# FRA_Sensor_TGS2xxx.net
KiCad netlist of a schematic drawn in EAGLE
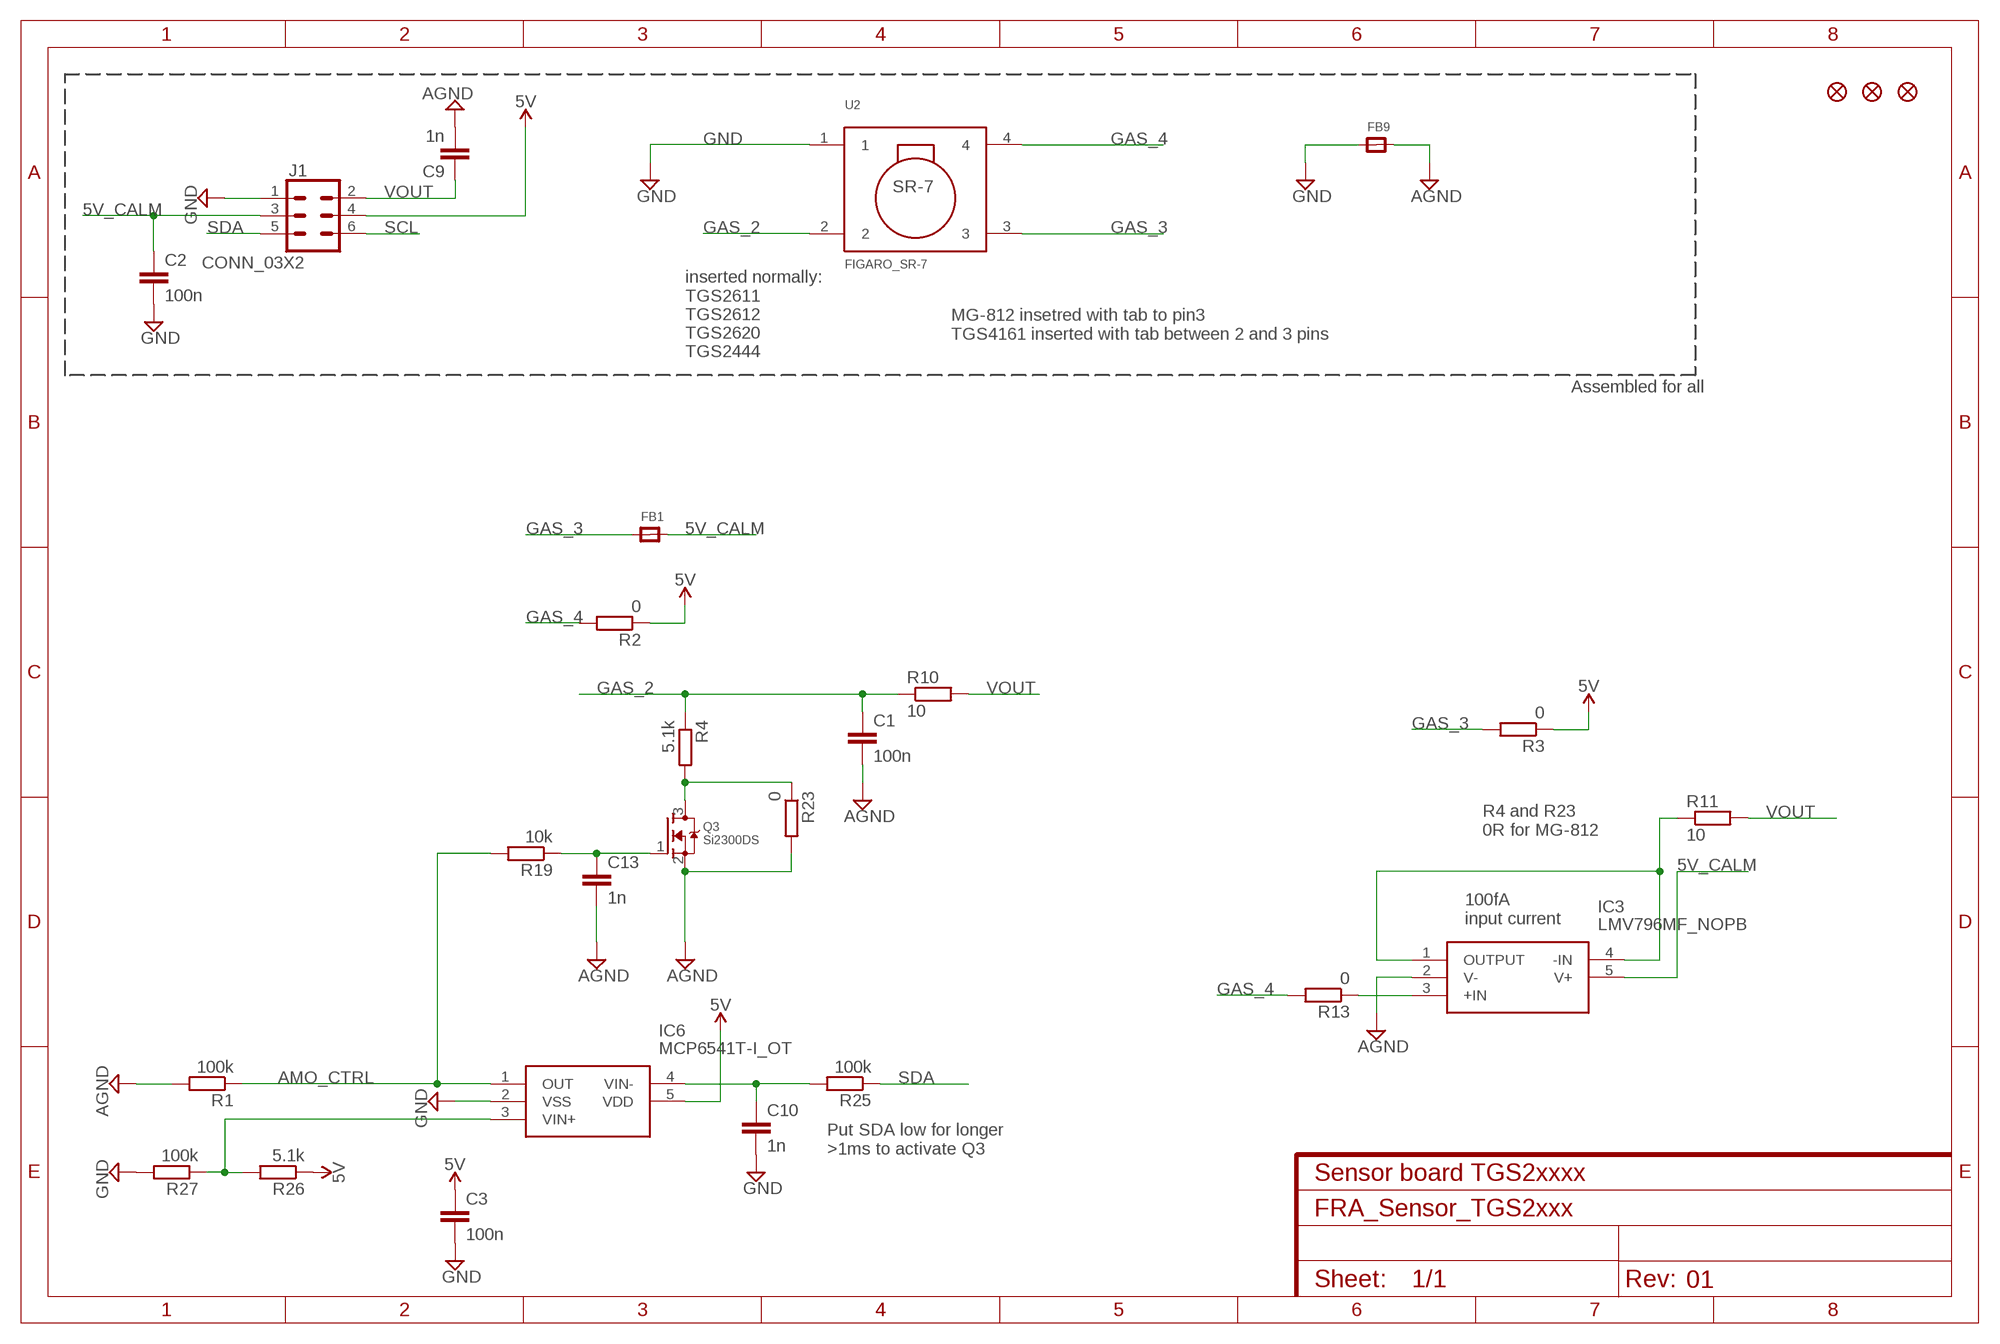
[diagram p0: schematic, sheet 1]

(export (version "E")
  (design (tool "Eeschema 10.0.6"))
  (components
    (comp (ref "C1")
      (value "100n")
      (footprint "eagle-import:C0603K")
      (fields (field (name "PARTNO") "GRM188R71C104KA01D"))
      (libsource (lib "eagle-import") (part "C-EUC0603K"))
    )
    (comp (ref "C2")
      (value "100n")
      (footprint "eagle-import:C0603K")
      (fields (field (name "PARTNO") "GRM188R71C104KA01D"))
      (libsource (lib "eagle-import") (part "C-EUC0603K"))
    )
    (comp (ref "C3")
      (value "100n")
      (footprint "eagle-import:C0603K")
      (fields (field (name "PARTNO") "GRM188R71C104KA01D"))
      (libsource (lib "eagle-import") (part "C-EUC0603K"))
    )
    (comp (ref "C9")
      (value "1n")
      (footprint "eagle-import:C0603K")
      (fields (field (name "PARTNO") "GRM188R71H102KA01D"))
      (libsource (lib "eagle-import") (part "C-EUC0603K"))
    )
    (comp (ref "C10")
      (value "1n")
      (footprint "eagle-import:C0603K")
      (fields (field (name "PARTNO") "GRM188R71H102KA01D"))
      (libsource (lib "eagle-import") (part "C-EUC0603K"))
    )
    (comp (ref "C13")
      (value "1n")
      (footprint "eagle-import:C0603K")
      (fields (field (name "PARTNO") "GRM188R71H102KA01D"))
      (libsource (lib "eagle-import") (part "C-EUC0603K"))
    )
    (comp (ref "FB1")
      (value "FERRITE")
      (footprint "eagle-import:0603")
      (fields (field (name "PARTNO") "BLM18PG121SN1D"))
      (libsource (lib "eagle-import") (part "FERRITE"))
    )
    (comp (ref "FB9")
      (value "FERRITE")
      (footprint "eagle-import:0603")
      (fields (field (name "PARTNO") "BLM18PG121SN1D"))
      (libsource (lib "eagle-import") (part "FERRITE"))
    )
    (comp (ref "FID1")
      (value "FIDUCIAL\"\"")
      (footprint "eagle-import:FIDUCIAL_1MM")
      (libsource (lib "eagle-import") (part "FIDUCIAL{dblquote}{dblquote}"))
    )
    (comp (ref "FID2")
      (value "FIDUCIAL\"\"")
      (footprint "eagle-import:FIDUCIAL_1MM")
      (libsource (lib "eagle-import") (part "FIDUCIAL{dblquote}{dblquote}"))
    )
    (comp (ref "FID4")
      (value "FIDUCIAL\"\"")
      (footprint "eagle-import:FIDUCIAL_1MM")
      (libsource (lib "eagle-import") (part "FIDUCIAL{dblquote}{dblquote}"))
    )
    (comp (ref "IC3")
      (value "LMV796MF_NOPB")
      (footprint "eagle-import:SOT95P280X145-5N")
      (fields
        (field (name "MANUFACTURER_PART_NUMBER") "LMV796MF/NOPB")
        (field (name "MOUSER_PART_NUMBER") "926-LMV796MF/NOPB")
        (field (name "PARTNO") "LMV796MF")
      )
      (libsource (lib "eagle-import") (part "LMV796MF_NOPB"))
    )
    (comp (ref "IC6")
      (value "MCP6541T-I_OT")
      (footprint "eagle-import:SOT95P270X145-5N")
      (fields
        (field (name "MANUFACTURER_PART_NUMBER") "MCP6541T-I/OT")
        (field (name "MOUSER_PART_NUMBER") "579-MCP6541T-I/OT")
      )
      (libsource (lib "eagle-import") (part "MCP6541T-I_OT"))
    )
    (comp (ref "J1")
      (value "CONN_03X2")
      (footprint "eagle-import:WE_61200621621")
      (fields (field (name "PARTNO") "30306-6002HB"))
      (libsource (lib "eagle-import") (part "CONN_03X2_WE_61200621621"))
    )
    (comp (ref "Q3")
      (value "Si2300DS")
      (footprint "eagle-import:SOT23")
      (fields (field (name "PARTNO") "SI2300DS-T1-GE3"))
      (libsource (lib "eagle-import") (part "MOSFET-NREFLOW"))
    )
    (comp (ref "R1")
      (value "100k")
      (footprint "eagle-import:R0603")
      (fields (field (name "PARTNO") "CRCW0603100KFKEA"))
      (libsource (lib "eagle-import") (part "R-EU_R0603"))
    )
    (comp (ref "R2")
      (value "0")
      (footprint "eagle-import:R0603")
      (fields (field (name "PARTNO") "CRCW06030000Z0EA"))
      (libsource (lib "eagle-import") (part "R-EU_R0603"))
    )
    (comp (ref "R3")
      (value "0")
      (footprint "eagle-import:R0603")
      (fields (field (name "PARTNO") "CRCW06030000Z0EA"))
      (libsource (lib "eagle-import") (part "R-EU_R0603"))
    )
    (comp (ref "R4")
      (value "5.1k")
      (footprint "eagle-import:R0603")
      (fields (field (name "PARTNO") "CRCW06035K10FKEA"))
      (libsource (lib "eagle-import") (part "R-EU_R0603"))
    )
    (comp (ref "R10")
      (value "10")
      (footprint "eagle-import:R0603")
      (fields (field (name "PARTNO") "CRCW060310R0FKEA"))
      (libsource (lib "eagle-import") (part "R-EU_R0603"))
    )
    (comp (ref "R11")
      (value "10")
      (footprint "eagle-import:R0603")
      (fields (field (name "PARTNO") "CRCW060310R0FKEA"))
      (libsource (lib "eagle-import") (part "R-EU_R0603"))
    )
    (comp (ref "R13")
      (value "0")
      (footprint "eagle-import:R0603")
      (fields (field (name "PARTNO") "CRCW06030000Z0EA"))
      (libsource (lib "eagle-import") (part "R-EU_R0603"))
    )
    (comp (ref "R19")
      (value "10k")
      (footprint "eagle-import:R0603")
      (fields (field (name "PARTNO") "CRCW060310K0FKEA"))
      (libsource (lib "eagle-import") (part "R-EU_R0603"))
    )
    (comp (ref "R23")
      (value "0")
      (footprint "eagle-import:R0603")
      (fields (field (name "PARTNO") "CRCW06030000Z0EA"))
      (libsource (lib "eagle-import") (part "R-EU_R0603"))
    )
    (comp (ref "R25")
      (value "100k")
      (footprint "eagle-import:R0603")
      (fields (field (name "PARTNO") "CRCW0603100KFKEA"))
      (libsource (lib "eagle-import") (part "R-EU_R0603"))
    )
    (comp (ref "R26")
      (value "5.1k")
      (footprint "eagle-import:R0603")
      (fields (field (name "PARTNO") "CRCW06035K10FKEA"))
      (libsource (lib "eagle-import") (part "R-EU_R0603"))
    )
    (comp (ref "R27")
      (value "100k")
      (footprint "eagle-import:R0603")
      (fields (field (name "PARTNO") "CRCW0603100KFKEA"))
      (libsource (lib "eagle-import") (part "R-EU_R0603"))
    )
    (comp (ref "U2")
      (value "FIGARO_SR-7")
      (footprint "eagle-import:FIGARO-SR7")
      (fields (field (name "PARTNO") "installed_by_customer"))
      (libsource (lib "eagle-import") (part "FIGARO_SR-7"))
    )
  )
  (nets
    (net (code "1") (name "/5V_CALM") (class "Default")
      (node (ref "C2") (pin "1") (pinfunction "1_1") (pintype "passive"))
      (node (ref "FB1") (pin "2") (pinfunction "P$2_2") (pintype "passive"))
      (node (ref "IC3") (pin "5") (pinfunction "V+_5") (pintype "bidirectional"))
      (node (ref "J1") (pin "3") (pinfunction "3_3") (pintype "bidirectional"))
    )
    (net (code "2") (name "/AMO_CTRL") (class "Default")
      (node (ref "IC6") (pin "1") (pinfunction "OUT_1") (pintype "output"))
      (node (ref "R1") (pin "1") (pinfunction "1_1") (pintype "passive"))
      (node (ref "R19") (pin "2") (pinfunction "2_2") (pintype "passive"))
    )
    (net (code "3") (name "/GAS_2") (class "Default")
      (node (ref "C1") (pin "1") (pinfunction "1_1") (pintype "passive"))
      (node (ref "R10") (pin "1") (pinfunction "1_1") (pintype "passive"))
      (node (ref "R4") (pin "1") (pinfunction "1_1") (pintype "passive"))
      (node (ref "U2") (pin "2") (pinfunction "2_2") (pintype "bidirectional"))
    )
    (net (code "4") (name "/GAS_3") (class "Default")
      (node (ref "FB1") (pin "1") (pinfunction "P$1_1") (pintype "passive"))
      (node (ref "R3") (pin "2") (pinfunction "2_2") (pintype "passive"))
      (node (ref "U2") (pin "3") (pinfunction "3_3") (pintype "bidirectional"))
    )
    (net (code "5") (name "/GAS_4") (class "Default")
      (node (ref "R13") (pin "2") (pinfunction "2_2") (pintype "passive"))
      (node (ref "R2") (pin "2") (pinfunction "2_2") (pintype "passive"))
      (node (ref "U2") (pin "4") (pinfunction "4_4") (pintype "bidirectional"))
    )
    (net (code "6") (name "/SCL") (class "Default")
      (node (ref "J1") (pin "6") (pinfunction "6_6") (pintype "bidirectional"))
    )
    (net (code "7") (name "/SDA") (class "Default")
      (node (ref "J1") (pin "5") (pinfunction "5_5") (pintype "bidirectional"))
      (node (ref "R25") (pin "1") (pinfunction "1_1") (pintype "passive"))
    )
    (net (code "8") (name "/VOUT") (class "Default")
      (node (ref "C9") (pin "1") (pinfunction "1_1") (pintype "passive"))
      (node (ref "J1") (pin "2") (pinfunction "2_2") (pintype "bidirectional"))
      (node (ref "R10") (pin "2") (pinfunction "2_2") (pintype "passive"))
      (node (ref "R11") (pin "2") (pinfunction "2_2") (pintype "passive"))
    )
    (net (code "9") (name "5V") (class "Default")
      (node (ref "C3") (pin "1") (pinfunction "1_1") (pintype "passive"))
      (node (ref "IC6") (pin "5") (pinfunction "VDD_5") (pintype "power_in"))
      (node (ref "J1") (pin "4") (pinfunction "4_4") (pintype "bidirectional"))
      (node (ref "R2") (pin "1") (pinfunction "1_1") (pintype "passive"))
      (node (ref "R26") (pin "1") (pinfunction "1_1") (pintype "passive"))
      (node (ref "R3") (pin "1") (pinfunction "1_1") (pintype "passive"))
    )
    (net (code "10") (name "AGND") (class "Default")
      (node (ref "C1") (pin "2") (pinfunction "2_2") (pintype "passive"))
      (node (ref "C13") (pin "2") (pinfunction "2_2") (pintype "passive"))
      (node (ref "C9") (pin "2") (pinfunction "2_2") (pintype "passive"))
      (node (ref "FB9") (pin "2") (pinfunction "P$2_2") (pintype "passive"))
      (node (ref "IC3") (pin "2") (pinfunction "V-_2") (pintype "bidirectional"))
      (node (ref "Q3") (pin "2") (pinfunction "S_2") (pintype "bidirectional"))
      (node (ref "R1") (pin "2") (pinfunction "2_2") (pintype "passive"))
      (node (ref "R23") (pin "2") (pinfunction "2_2") (pintype "passive"))
    )
    (net (code "11") (name "GND") (class "Default")
      (node (ref "C10") (pin "2") (pinfunction "2_2") (pintype "passive"))
      (node (ref "C2") (pin "2") (pinfunction "2_2") (pintype "passive"))
      (node (ref "C3") (pin "2") (pinfunction "2_2") (pintype "passive"))
      (node (ref "FB9") (pin "1") (pinfunction "P$1_1") (pintype "passive"))
      (node (ref "IC6") (pin "2") (pinfunction "VSS_2") (pintype "power_in"))
      (node (ref "J1") (pin "1") (pinfunction "1_1") (pintype "bidirectional"))
      (node (ref "R27") (pin "2") (pinfunction "2_2") (pintype "passive"))
      (node (ref "U2") (pin "1") (pinfunction "1_1") (pintype "bidirectional"))
    )
    (net (code "12") (name "Net-(IC3-+IN)") (class "Default")
      (node (ref "IC3") (pin "3") (pinfunction "+IN_3") (pintype "input"))
      (node (ref "R13") (pin "1") (pinfunction "1_1") (pintype "passive"))
    )
    (net (code "13") (name "Net-(IC3--IN)") (class "Default")
      (node (ref "IC3") (pin "1") (pinfunction "OUTPUT_1") (pintype "output"))
      (node (ref "IC3") (pin "4") (pinfunction "-IN_4") (pintype "input"))
      (node (ref "R11") (pin "1") (pinfunction "1_1") (pintype "passive"))
    )
    (net (code "14") (name "Net-(IC6-VIN+)") (class "Default")
      (node (ref "IC6") (pin "3") (pinfunction "VIN+_3") (pintype "input"))
      (node (ref "R26") (pin "2") (pinfunction "2_2") (pintype "passive"))
      (node (ref "R27") (pin "1") (pinfunction "1_1") (pintype "passive"))
    )
    (net (code "15") (name "Net-(IC6-VIN-)") (class "Default")
      (node (ref "C10") (pin "1") (pinfunction "1_1") (pintype "passive"))
      (node (ref "IC6") (pin "4") (pinfunction "VIN-_4") (pintype "input"))
      (node (ref "R25") (pin "2") (pinfunction "2_2") (pintype "passive"))
    )
    (net (code "16") (name "Net-(Q3-D)") (class "Default")
      (node (ref "Q3") (pin "3") (pinfunction "D_3") (pintype "bidirectional"))
      (node (ref "R23") (pin "1") (pinfunction "1_1") (pintype "passive"))
      (node (ref "R4") (pin "2") (pinfunction "2_2") (pintype "passive"))
    )
    (net (code "17") (name "Net-(Q3-G)") (class "Default")
      (node (ref "C13") (pin "1") (pinfunction "1_1") (pintype "passive"))
      (node (ref "Q3") (pin "1") (pinfunction "G_1") (pintype "bidirectional"))
      (node (ref "R19") (pin "1") (pinfunction "1_1") (pintype "passive"))
    )
  )
)
